# twilight-photometer-1.net
KiCad netlist of a schematic drawn in EAGLE
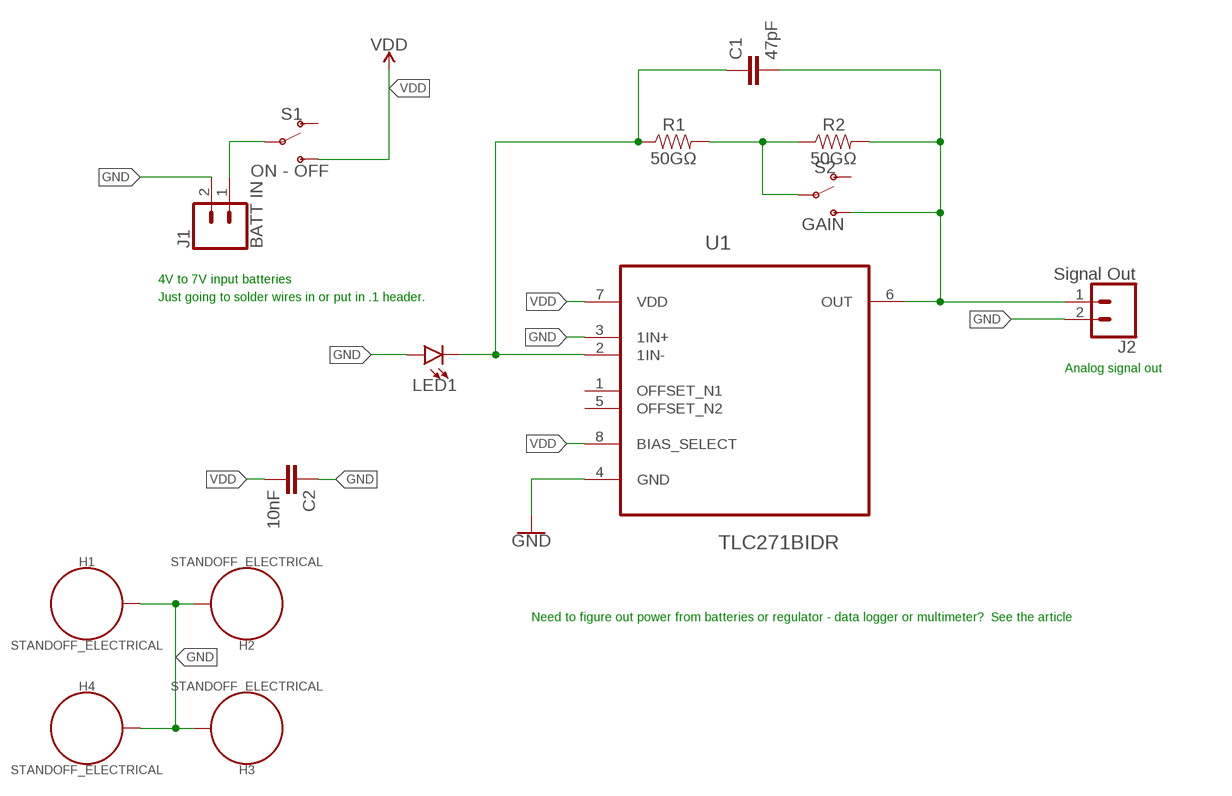
[diagram p0: schematic, sheet 1]

(export (version "E")
  (design (tool "Eeschema 10.0.6"))
  (components
    (comp (ref "C1")
      (value "47pF")
      (footprint "eagle-import:0603")
      (libsource (lib "eagle-import") (part "47PF-0603-50V-5%"))
    )
    (comp (ref "C2")
      (value "10nF")
      (footprint "eagle-import:0603")
      (libsource (lib "eagle-import") (part "10NF-0603-50V-10%"))
    )
    (comp (ref "H1")
      (value "STANDOFF_ELECTRICAL")
      (footprint "eagle-import:STANDOFF-ELECTRICAL")
      (libsource (lib "eagle-import") (part "STANDOFF_ELECTRICAL"))
    )
    (comp (ref "H2")
      (value "STANDOFF_ELECTRICAL")
      (footprint "eagle-import:STANDOFF-ELECTRICAL")
      (libsource (lib "eagle-import") (part "STANDOFF_ELECTRICAL"))
    )
    (comp (ref "H3")
      (value "STANDOFF_ELECTRICAL")
      (footprint "eagle-import:STANDOFF-ELECTRICAL")
      (libsource (lib "eagle-import") (part "STANDOFF_ELECTRICAL"))
    )
    (comp (ref "H4")
      (value "STANDOFF_ELECTRICAL")
      (footprint "eagle-import:STANDOFF-ELECTRICAL")
      (libsource (lib "eagle-import") (part "STANDOFF_ELECTRICAL"))
    )
    (comp (ref "J1")
      (value "BATT IN")
      (footprint "eagle-import:1X02_LOCK_LONGPADS")
      (libsource (lib "eagle-import") (part "CONN_02LOCK_LONGPADS"))
    )
    (comp (ref "J2")
      (value "Signal Out")
      (footprint "eagle-import:1X02_LOCK_LONGPADS")
      (libsource (lib "eagle-import") (part "CONN_02LOCK_LONGPADS"))
    )
    (comp (ref "LED1")
      (value "LED5MM")
      (footprint "eagle-import:LED_5MM")
      (libsource (lib "eagle-import") (part "LED5MM"))
    )
    (comp (ref "R1")
      (value "50GΩ")
      (footprint "eagle-import:0805")
      (libsource (lib "eagle-import") (part "RESISTOR0805"))
    )
    (comp (ref "R2")
      (value "50GΩ")
      (footprint "eagle-import:0805")
      (libsource (lib "eagle-import") (part "RESISTOR0805"))
    )
    (comp (ref "S1")
      (value "ON - OFF")
      (footprint "eagle-import:SWITCH_SPDT_PTH_11.6X4.0MM_LOCK")
      (libsource (lib "eagle-import") (part "SWITCH-SPDT-PTH-11.6X4.0MM-LOCK"))
    )
    (comp (ref "S2")
      (value "GAIN")
      (footprint "eagle-import:SWITCH_SPDT_PTH_11.6X4.0MM_LOCK")
      (libsource (lib "eagle-import") (part "SWITCH-SPDT-PTH-11.6X4.0MM-LOCK"))
    )
    (comp (ref "U1")
      (value "TLC271BIDR")
      (footprint "eagle-import:SOIC127P600X175-8N")
      (fields (field (name "MPN") "TLC271ACD"))
      (libsource (lib "eagle-import") (part "TLC271ACD"))
    )
  )
  (nets
    (net (code "1") (name "GND") (class "Default")
      (node (ref "C2") (pin "1") (pinfunction "1_1") (pintype "passive"))
      (node (ref "H1") (pin "P1") (pinfunction "P$1_P1") (pintype "bidirectional"))
      (node (ref "H2") (pin "P1") (pinfunction "P$1_P1") (pintype "bidirectional"))
      (node (ref "H3") (pin "P1") (pinfunction "P$1_P1") (pintype "bidirectional"))
      (node (ref "H4") (pin "P1") (pinfunction "P$1_P1") (pintype "bidirectional"))
      (node (ref "J1") (pin "2") (pinfunction "2_2") (pintype "passive"))
      (node (ref "J2") (pin "2") (pinfunction "2_2") (pintype "passive"))
      (node (ref "LED1") (pin "A") (pinfunction "A_A") (pintype "passive"))
      (node (ref "U1") (pin "3") (pinfunction "1IN+_3") (pintype "input"))
      (node (ref "U1") (pin "4") (pinfunction "GND_4") (pintype "passive"))
    )
    (net (code "2") (name "Net-(LED1-C)") (class "Default")
      (node (ref "C1") (pin "1") (pinfunction "1_1") (pintype "passive"))
      (node (ref "LED1") (pin "K") (pinfunction "C_K") (pintype "passive"))
      (node (ref "R1") (pin "1") (pinfunction "1_1") (pintype "passive"))
      (node (ref "U1") (pin "2") (pinfunction "1IN-_2") (pintype "input"))
    )
    (net (code "3") (name "Net-(S1-P)") (class "Default")
      (node (ref "J1") (pin "1") (pinfunction "1_1") (pintype "passive"))
      (node (ref "S1") (pin "2") (pinfunction "P_2") (pintype "passive"))
    )
    (net (code "4") (name "Net-(S2-P)") (class "Default")
      (node (ref "R1") (pin "2") (pinfunction "2_2") (pintype "passive"))
      (node (ref "R2") (pin "1") (pinfunction "1_1") (pintype "passive"))
      (node (ref "S2") (pin "2") (pinfunction "P_2") (pintype "passive"))
    )
    (net (code "5") (name "Net-(S2-S)") (class "Default")
      (node (ref "C1") (pin "2") (pinfunction "2_2") (pintype "passive"))
      (node (ref "J2") (pin "1") (pinfunction "1_1") (pintype "passive"))
      (node (ref "R2") (pin "2") (pinfunction "2_2") (pintype "passive"))
      (node (ref "S2") (pin "3") (pinfunction "S_3") (pintype "passive"))
      (node (ref "U1") (pin "6") (pinfunction "OUT_6") (pintype "output"))
    )
    (net (code "6") (name "VDD") (class "Default")
      (node (ref "C2") (pin "2") (pinfunction "2_2") (pintype "passive"))
      (node (ref "S1") (pin "3") (pinfunction "S_3") (pintype "passive"))
      (node (ref "U1") (pin "7") (pinfunction "VDD_7") (pintype "power_in"))
      (node (ref "U1") (pin "8") (pinfunction "BIAS_SELECT_8") (pintype "passive"))
    )
    (net (code "7") (name "unconnected-(S1-O-Pad1)") (class "Default")
      (node (ref "S1") (pin "1") (pinfunction "O_1") (pintype "passive"))
    )
    (net (code "8") (name "unconnected-(S2-O-Pad1)") (class "Default")
      (node (ref "S2") (pin "1") (pinfunction "O_1") (pintype "passive"))
    )
    (net (code "9") (name "unconnected-(U1-OFFSET_N1-Pad1)") (class "Default")
      (node (ref "U1") (pin "1") (pinfunction "OFFSET_N1_1") (pintype "input"))
    )
    (net (code "10") (name "unconnected-(U1-OFFSET_N2-Pad5)") (class "Default")
      (node (ref "U1") (pin "5") (pinfunction "OFFSET_N2_5") (pintype "input"))
    )
  )
)
